# gatedriverexample.net
KiCad netlist of a schematic drawn in EAGLE
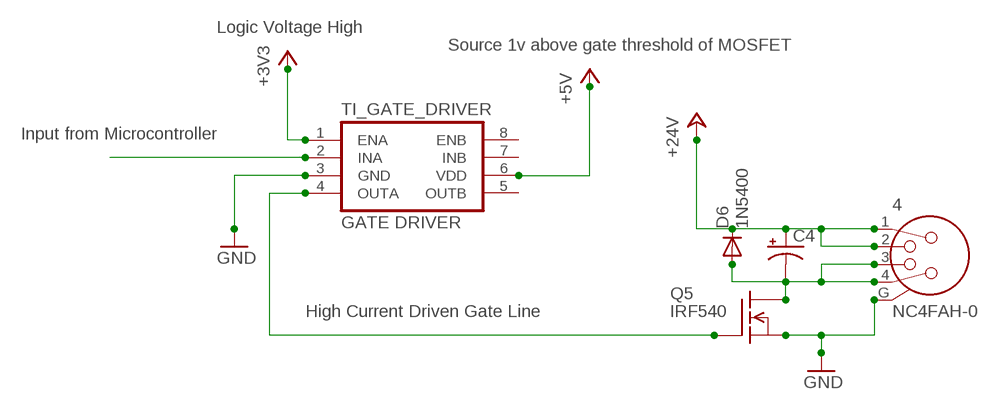
[diagram p0: schematic, sheet 1]

(export (version "E")
  (design (tool "Eeschema 10.0.6"))
  (components
    (comp (ref "4")
      (value "NC4FAH-0")
      (footprint "eagle-import:NC4FAH-0")
      (libsource (lib "eagle-import") (part "NC4FAH-0"))
    )
    (comp (ref "C4")
      (value "CPOL-USE2.5-6")
      (footprint "eagle-import:E2,5-6")
      (libsource (lib "eagle-import") (part "CPOL-USE2.5-6"))
    )
    (comp (ref "D6")
      (value "1N5400")
      (footprint "eagle-import:DO201-15")
      (libsource (lib "eagle-import") (part "1N5400"))
    )
    (comp (ref "Q5")
      (value "IRF540")
      (footprint "eagle-import:TO220")
      (libsource (lib "eagle-import") (part "IRF540"))
    )
    (comp (ref "TI_GATE_DRIVER")
      (value "GATE DRIVER")
      (footprint "eagle-import:SOIC-8")
      (libsource (lib "eagle-import") (part "IC_555-SOIC8"))
    )
  )
  (nets
    (net (code "1") (name "+3V3") (class "Default")
      (node (ref "TI_GATE_DRIVER") (pin "1") (pinfunction "ENA_1") (pintype "power_in"))
    )
    (net (code "2") (name "+5V") (class "Default")
      (node (ref "TI_GATE_DRIVER") (pin "6") (pinfunction "VDD_6") (pintype "input"))
    )
    (net (code "3") (name "+24V") (class "Default")
      (node (ref "4") (pin "1") (pinfunction "1_1") (pintype "passive"))
      (node (ref "4") (pin "2") (pinfunction "2_2") (pintype "passive"))
      (node (ref "C4") (pin "+") (pinfunction "+_+") (pintype "passive"))
      (node (ref "D6") (pin "C") (pinfunction "C_C") (pintype "passive"))
    )
    (net (code "4") (name "/ENB") (class "Default")
      (node (ref "TI_GATE_DRIVER") (pin "8") (pinfunction "ENB_8") (pintype "power_in"))
    )
    (net (code "5") (name "/OUTB") (class "Default")
      (node (ref "TI_GATE_DRIVER") (pin "5") (pinfunction "OUTB_5") (pintype "power_in"))
    )
    (net (code "6") (name "GND") (class "Default")
      (node (ref "4") (pin "G") (pinfunction "G_G") (pintype "passive"))
      (node (ref "Q5") (pin "3") (pinfunction "S_3") (pintype "passive"))
      (node (ref "TI_GATE_DRIVER") (pin "3") (pinfunction "GND_3") (pintype "output"))
    )
    (net (code "7") (name "Net-(Q5-D)") (class "Default")
      (node (ref "4") (pin "3") (pinfunction "3_3") (pintype "passive"))
      (node (ref "4") (pin "4") (pinfunction "4_4") (pintype "passive"))
      (node (ref "C4") (pin "-") (pinfunction "-_-") (pintype "passive"))
      (node (ref "D6") (pin "A") (pinfunction "A_A") (pintype "passive"))
      (node (ref "Q5") (pin "2") (pinfunction "D_2") (pintype "passive"))
    )
    (net (code "8") (name "Net-(Q5-G)") (class "Default")
      (node (ref "Q5") (pin "1") (pinfunction "G_1") (pintype "passive"))
      (node (ref "TI_GATE_DRIVER") (pin "4") (pinfunction "OUTA_4") (pintype "input"))
    )
    (net (code "9") (name "unconnected-(TI_GATE_DRIVER-INA-Pad2)") (class "Default")
      (node (ref "TI_GATE_DRIVER") (pin "2") (pinfunction "INA_2") (pintype "input"))
    )
    (net (code "10") (name "unconnected-(TI_GATE_DRIVER-INB-Pad7)") (class "Default")
      (node (ref "TI_GATE_DRIVER") (pin "7") (pinfunction "INB_7") (pintype "input"))
    )
  )
)
